# MP_TTL_UART_USB.net
KiCad netlist of a schematic drawn in Altium Designer
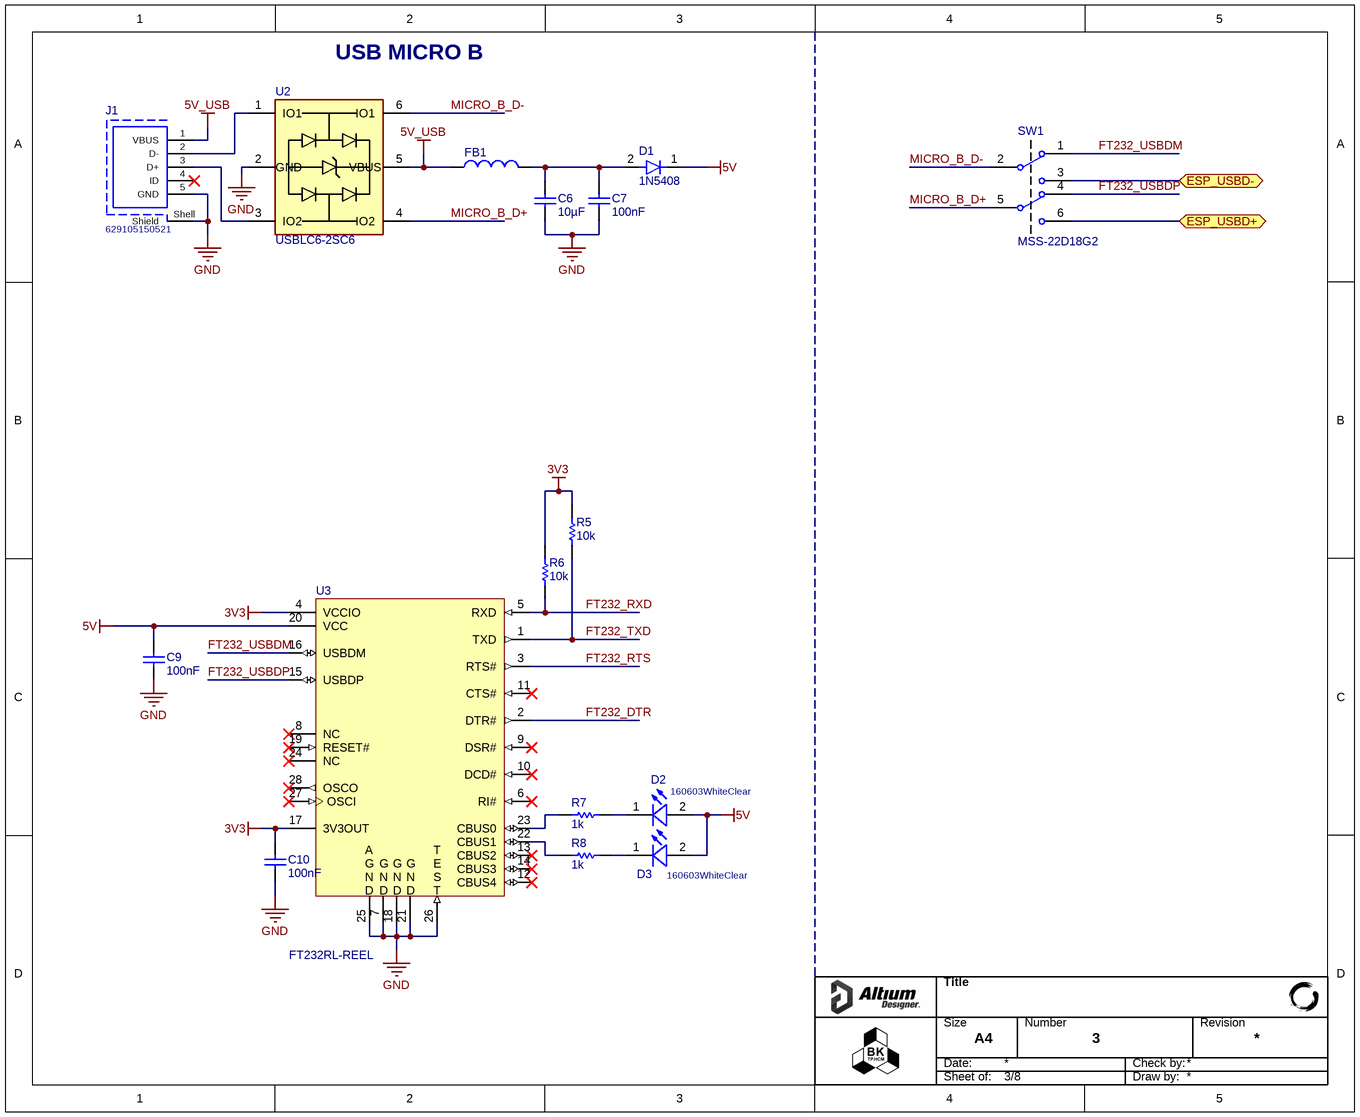
[diagram p0: [MP] TTL UART USB.SchDoc]

(export (version "E")
  (design (tool "Eeschema 10.0.6"))
  (components
    (comp (ref "C6")
      (value "10µF")
      (footprint "CAP_0603")
      (description "CAP, size 0603, 10 uF, 10 VDC, 10%")
      (fields
        (field (name "MANUFACTURER") "Samsung Electro-Mechanics")
        (field (name "LCSC PART #") "C19702")
        (field (name "SOURCE") "Capacitor_0603_10_percent.SchLib")
      )
      (libsource (lib "University of Technology") (part "010603475106.3"))
    )
    (comp (ref "C7")
      (value "100nF")
      (footprint "CAP_0603")
      (description "CAP, size 0603, 100 nF, 50 VDC, 10%")
      (fields
        (field (name "MANUFACTURER PART NUMBER") "CGA3E3X8R1H104K080AE")
        (field (name "LCSC PART #") "C14663")
        (field (name "SOURCE") "Capacitor_0603_10_percent.SchLib")
      )
      (libsource (lib "University of Technology") (part "010603475106.3"))
    )
    (comp (ref "C9")
      (value "100nF")
      (footprint "CAP_0603")
      (description "CAP, size 0603, 100 nF, 50 VDC, 10%")
      (fields
        (field (name "MANUFACTURER PART NUMBER") "CGA3E3X8R1H104K080AE")
        (field (name "LCSC PART #") "C14663")
        (field (name "SOURCE") "Capacitor_0603_10_percent.SchLib")
      )
      (libsource (lib "University of Technology") (part "010603475106.3"))
    )
    (comp (ref "C10")
      (value "100nF")
      (footprint "CAP_0603")
      (description "CAP, size 0603, 100 nF, 50 VDC, 10%")
      (fields
        (field (name "MANUFACTURER PART NUMBER") "CGA3E3X8R1H104K080AE")
        (field (name "LCSC PART #") "C14663")
        (field (name "SOURCE") "Capacitor_0603_10_percent.SchLib")
      )
      (libsource (lib "University of Technology") (part "010603475106.3"))
    )
    (comp (ref "D1")
      (value "1N5408")
      (footprint "FAIR-SMA-2_B_V")
      (description "Rectifier Diode, Schottky, 1 Phase, 1 Element, 3A, 1KV, Silicon")
      (libsource (lib "University of Technology") (part "1N5408"))
    )
    (comp (ref "D2")
      (value "160603WhiteClear")
      (footprint "WL-SMCW_0603_H=0.7mm")
      (description "WL-SMCW SMT Mono-color Chip LED Waterclear, size 0603, White")
      (libsource (lib "University of Technology") (part "160603WhiteClear"))
    )
    (comp (ref "D3")
      (value "160603WhiteClear")
      (footprint "WL-SMCW_0603_H=0.7mm")
      (description "WL-SMCW SMT Mono-color Chip LED Waterclear, size 0603, White")
      (libsource (lib "University of Technology") (part "160603WhiteClear"))
    )
    (comp (ref "FB1")
      (value "CBG160808U601T")
      (footprint "CBG160808U601T-Footprint")
      (description "0603 600Ω ±25% DCR=0.5Ω 0.2A")
      (libsource (lib "University of Technology") (part "IND-2_1"))
    )
    (comp (ref "J1")
      (value "629105150521")
      (footprint "629105150521")
      (description "Micro USB 2.0 Type B Receptacle WR-COM, Horizontal, SMT, with Pegs, High Current at Pin 1 & Pin 5")
      (libsource (lib "University of Technology") (part "Micro USB 2.0"))
    )
    (comp (ref "R5")
      (value "10k")
      (footprint "RES_0603")
      (description "RES, size 0603, 10 KOhm, 1/10 W, 1%")
      (fields
        (field (name "MANUFACTURER PART NUMBER") "RC0603FR-0710KL")
        (field (name "MANUFACTURER") "YAGEO")
      )
      (libsource (lib "University of Technology") (part "00060371541"))
    )
    (comp (ref "R6")
      (value "10k")
      (footprint "RES_0603")
      (description "RES, size 0603, 10 KOhm, 1/10 W, 1%")
      (fields
        (field (name "MANUFACTURER PART NUMBER") "RC0603FR-0710KL")
        (field (name "MANUFACTURER") "YAGEO")
      )
      (libsource (lib "University of Technology") (part "00060371541"))
    )
    (comp (ref "R7")
      (value "1k")
      (footprint "RES_0603")
      (description "RES, size 0603, 1 KOhm, 1/10 W, 1%")
      (fields (field (name "TOLERANCE") "1%") (field (name "MANUFACTURER PART NUMBER") "RC0603FR-071KL"))
      (libsource (lib "University of Technology") (part "00060371541"))
    )
    (comp (ref "R8")
      (value "1k")
      (footprint "RES_0603")
      (description "RES, size 0603, 1 KOhm, 1/10 W, 1%")
      (fields (field (name "TOLERANCE") "1%") (field (name "MANUFACTURER PART NUMBER") "RC0603FR-071KL"))
      (libsource (lib "University of Technology") (part "00060371541"))
    )
    (comp (ref "SW1")
      (value "MSS-22D18G2")
      (footprint "MSS-22D18G2")
      (description "Slide switch 2.5")
      (libsource (lib "University of Technology") (part "MSS-22D18G2"))
    )
    (comp (ref "U2")
      (value "USBLC6-2SC6")
      (footprint "USBLC6-2SC6-Footprint-1")
      (description "17V Clamp 5A (8/20Âµs) Ipp Tvs Diode Surface Mount SOT-23-6")
      (libsource (lib "University of Technology") (part "USBLC6"))
    )
    (comp (ref "U3")
      (value "FT232RL-REEL")
      (footprint "FTDI-SSOP-28_L")
      (description "USB UART IC, -0.5 to 6 V, 24 mA, -40 to 85 degC, 28-Pin SSOP, RoHS, Tape and Reel")
      (fields (field (name "MANUFACTURER") "Future Technology Devices International (FTDI)"))
      (libsource (lib "University of Technology") (part "FTDI-FT232-SSOP-28"))
    )
  )
  (nets
    (net (code "1") (name "/ESP_USBD+") (class "Default")
      (node (ref "SW1") (pin "6") (pinfunction "2-2_6") (pintype "passive"))
    )
    (net (code "2") (name "/ESP_USBD-") (class "Default")
      (node (ref "SW1") (pin "3") (pinfunction "1-2_3") (pintype "passive"))
    )
    (net (code "3") (name "/FT232_DTR") (class "Default")
      (node (ref "U3") (pin "2") (pinfunction "DTR#_2") (pintype "output"))
    )
    (net (code "4") (name "/FT232_RTS") (class "Default")
      (node (ref "U3") (pin "3") (pinfunction "RTS#_3") (pintype "output"))
    )
    (net (code "5") (name "/FT232_RXD") (class "Default")
      (node (ref "R6") (pin "1") (pinfunction "1_1") (pintype "passive"))
      (node (ref "U3") (pin "5") (pinfunction "RXD_5") (pintype "input"))
    )
    (net (code "6") (name "/FT232_TXD") (class "Default")
      (node (ref "R5") (pin "1") (pinfunction "1_1") (pintype "passive"))
      (node (ref "U3") (pin "1") (pinfunction "TXD_1") (pintype "output"))
    )
    (net (code "7") (name "/FT232_USBDM") (class "Default")
      (node (ref "SW1") (pin "1") (pinfunction "1-1_1") (pintype "passive"))
      (node (ref "U3") (pin "16") (pinfunction "USBDM_16") (pintype "bidirectional"))
    )
    (net (code "8") (name "/FT232_USBDP") (class "Default")
      (node (ref "SW1") (pin "4") (pinfunction "2-1_4") (pintype "passive"))
      (node (ref "U3") (pin "15") (pinfunction "USBDP_15") (pintype "bidirectional"))
    )
    (net (code "9") (name "/MICRO_B_D+") (class "Default")
      (node (ref "SW1") (pin "5") (pinfunction "COM2_5") (pintype "passive"))
      (node (ref "U2") (pin "4") (pinfunction "IO2_4") (pintype "passive"))
    )
    (net (code "10") (name "/MICRO_B_D-") (class "Default")
      (node (ref "SW1") (pin "2") (pinfunction "COM1_2") (pintype "passive"))
      (node (ref "U2") (pin "6") (pinfunction "IO1_6") (pintype "passive"))
    )
    (net (code "11") (name "3V3") (class "Default")
      (node (ref "C10") (pin "2") (pinfunction "2_2") (pintype "passive"))
      (node (ref "R5") (pin "2") (pinfunction "2_2") (pintype "passive"))
      (node (ref "R6") (pin "2") (pinfunction "2_2") (pintype "passive"))
      (node (ref "U3") (pin "17") (pinfunction "3V3OUT_17") (pintype "power_in"))
      (node (ref "U3") (pin "4") (pinfunction "VCCIO_4") (pintype "power_in"))
    )
    (net (code "12") (name "5V") (class "Default")
      (node (ref "C9") (pin "2") (pinfunction "2_2") (pintype "passive"))
      (node (ref "D1") (pin "1") (pinfunction "K_1") (pintype "passive"))
      (node (ref "D2") (pin "2") (pinfunction "A_2") (pintype "passive"))
      (node (ref "D3") (pin "2") (pinfunction "A_2") (pintype "passive"))
      (node (ref "U3") (pin "20") (pinfunction "VCC_20") (pintype "power_in"))
    )
    (net (code "13") (name "5V_USB") (class "Default")
      (node (ref "FB1") (pin "1") (pinfunction "1_1") (pintype "passive"))
      (node (ref "J1") (pin "1") (pinfunction "VBUS_1") (pintype "passive"))
      (node (ref "U2") (pin "5") (pinfunction "VBUS_5") (pintype "power_in"))
    )
    (net (code "14") (name "GND") (class "Default")
      (node (ref "C10") (pin "1") (pinfunction "1_1") (pintype "passive"))
      (node (ref "C6") (pin "1") (pinfunction "1_1") (pintype "passive"))
      (node (ref "C7") (pin "2") (pinfunction "2_2") (pintype "passive"))
      (node (ref "C9") (pin "1") (pinfunction "1_1") (pintype "passive"))
      (node (ref "J1") (pin "5") (pinfunction "GND_5") (pintype "passive"))
      (node (ref "J1") (pin "Shell") (pinfunction "Shield_Shell") (pintype "passive"))
      (node (ref "U2") (pin "2") (pinfunction "GND_2") (pintype "power_in"))
      (node (ref "U3") (pin "18") (pinfunction "GND_18") (pintype "power_in"))
      (node (ref "U3") (pin "21") (pinfunction "GND_21") (pintype "power_in"))
      (node (ref "U3") (pin "25") (pinfunction "AGND_25") (pintype "power_in"))
      (node (ref "U3") (pin "26") (pinfunction "TEST_26") (pintype "input"))
      (node (ref "U3") (pin "7") (pinfunction "GND_7") (pintype "power_in"))
    )
    (net (code "15") (name "Net-(D1-A)") (class "Default")
      (node (ref "C6") (pin "2") (pinfunction "2_2") (pintype "passive"))
      (node (ref "C7") (pin "1") (pinfunction "1_1") (pintype "passive"))
      (node (ref "D1") (pin "2") (pinfunction "A_2") (pintype "passive"))
      (node (ref "FB1") (pin "2") (pinfunction "2_2") (pintype "passive"))
    )
    (net (code "16") (name "Net-(D2-K)") (class "Default")
      (node (ref "D2") (pin "1") (pinfunction "K_1") (pintype "passive"))
      (node (ref "R7") (pin "1") (pinfunction "1_1") (pintype "passive"))
    )
    (net (code "17") (name "Net-(D3-K)") (class "Default")
      (node (ref "D3") (pin "1") (pinfunction "K_1") (pintype "passive"))
      (node (ref "R8") (pin "1") (pinfunction "1_1") (pintype "passive"))
    )
    (net (code "18") (name "Net-(J1-D+)") (class "Default")
      (node (ref "J1") (pin "3") (pinfunction "D+_3") (pintype "passive"))
      (node (ref "U2") (pin "3") (pinfunction "IO2_3") (pintype "passive"))
    )
    (net (code "19") (name "Net-(J1-D-)") (class "Default")
      (node (ref "J1") (pin "2") (pinfunction "D-_2") (pintype "passive"))
      (node (ref "U2") (pin "1") (pinfunction "IO1_1") (pintype "passive"))
    )
    (net (code "20") (name "Net-(U3-CBUS0)") (class "Default")
      (node (ref "R7") (pin "2") (pinfunction "2_2") (pintype "passive"))
      (node (ref "U3") (pin "23") (pinfunction "CBUS0_23") (pintype "bidirectional"))
    )
    (net (code "21") (name "Net-(U3-CBUS1)") (class "Default")
      (node (ref "R8") (pin "2") (pinfunction "2_2") (pintype "passive"))
      (node (ref "U3") (pin "22") (pinfunction "CBUS1_22") (pintype "bidirectional"))
    )
    (net (code "22") (name "unconnected-(J1-ID-Pad4)") (class "Default")
      (node (ref "J1") (pin "4") (pinfunction "ID_4") (pintype "passive+no_connect"))
    )
    (net (code "23") (name "unconnected-(U3-CBUS2-Pad13)") (class "Default")
      (node (ref "U3") (pin "13") (pinfunction "CBUS2_13") (pintype "bidirectional+no_connect"))
    )
    (net (code "24") (name "unconnected-(U3-CBUS3-Pad14)") (class "Default")
      (node (ref "U3") (pin "14") (pinfunction "CBUS3_14") (pintype "bidirectional+no_connect"))
    )
    (net (code "25") (name "unconnected-(U3-CBUS4-Pad12)") (class "Default")
      (node (ref "U3") (pin "12") (pinfunction "CBUS4_12") (pintype "bidirectional+no_connect"))
    )
    (net (code "26") (name "unconnected-(U3-CTS#-Pad11)") (class "Default")
      (node (ref "U3") (pin "11") (pinfunction "CTS#_11") (pintype "input+no_connect"))
    )
    (net (code "27") (name "unconnected-(U3-DCD#-Pad10)") (class "Default")
      (node (ref "U3") (pin "10") (pinfunction "DCD#_10") (pintype "input+no_connect"))
    )
    (net (code "28") (name "unconnected-(U3-DSR#-Pad9)") (class "Default")
      (node (ref "U3") (pin "9") (pinfunction "DSR#_9") (pintype "input+no_connect"))
    )
    (net (code "29") (name "unconnected-(U3-NC-Pad8)") (class "Default")
      (node (ref "U3") (pin "8") (pinfunction "NC_8") (pintype "passive+no_connect"))
    )
    (net (code "30") (name "unconnected-(U3-NC-Pad24)") (class "Default")
      (node (ref "U3") (pin "24") (pinfunction "NC_24") (pintype "passive+no_connect"))
    )
    (net (code "31") (name "unconnected-(U3-OSCI-Pad27)") (class "Default")
      (node (ref "U3") (pin "27") (pinfunction "OSCI_27") (pintype "input+no_connect"))
    )
    (net (code "32") (name "unconnected-(U3-OSCO-Pad28)") (class "Default")
      (node (ref "U3") (pin "28") (pinfunction "OSCO_28") (pintype "output+no_connect"))
    )
    (net (code "33") (name "unconnected-(U3-RESET#-Pad19)") (class "Default")
      (node (ref "U3") (pin "19") (pinfunction "RESET#_19") (pintype "input+no_connect"))
    )
    (net (code "34") (name "unconnected-(U3-RI#-Pad6)") (class "Default")
      (node (ref "U3") (pin "6") (pinfunction "RI#_6") (pintype "input+no_connect"))
    )
  )
)
